# USBCONN_A_short.net
KiCad netlist of a schematic drawn in Altium Designer
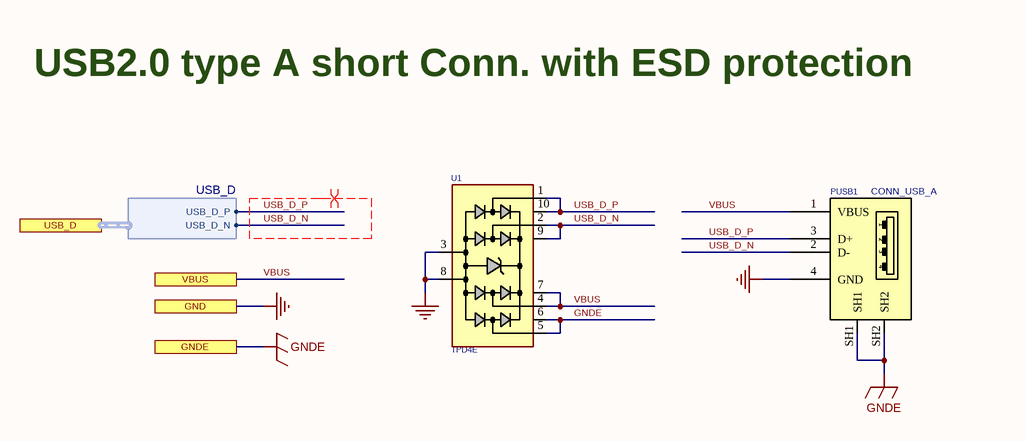
[diagram p0: USBCONN_A_short.SchDoc]

(export (version "E")
  (design (tool "Eeschema 10.0.6"))
  (components
    (comp (ref "PUSB1")
      (value "CONN_USB_A")
      (footprint "USB_A_REC_RA_THD_S")
      (description "CONN, USB, A, RECEPTACLE, R/A, THD")
      (fields (field (name "MANF_P#") "USB1125"))
      (libsource (lib "conn_usb") (part "CONN_USB_A_REC_RA_THD_SHORT"))
    )
    (comp (ref "U1")
      (value "TPD4E")
      (footprint "SON50_10_2510")
      (description "TVS, ESD PROTECT, 4CH,")
      (fields (field (name "MANF_P#") "TPD4E05U06DQA") (field (name "MANF") "Texas Instruments"))
      (libsource (lib "protect_tvs_esd_fuse") (part "TVS_X4_TPD4E05U06"))
    )
  )
  (nets
    (net (code "2") (name "/USB_D_N") (class "Default")
      (node (ref "PUSB1") (pin "2") (pinfunction "D-_2") (pintype "passive"))
      (node (ref "U1") (pin "2") (pinfunction "2_2") (pintype "passive"))
      (node (ref "U1") (pin "9") (pinfunction "9_9") (pintype "passive"))
    )
    (net (code "3") (name "/USB_D_P") (class "Default")
      (node (ref "PUSB1") (pin "3") (pinfunction "D+_3") (pintype "passive"))
      (node (ref "U1") (pin "1") (pinfunction "1_1") (pintype "passive"))
      (node (ref "U1") (pin "10") (pinfunction "10_10") (pintype "passive"))
    )
    (net (code "4") (name "/VBUS") (class "Default")
      (node (ref "PUSB1") (pin "1") (pinfunction "VBUS_1") (pintype "passive"))
      (node (ref "U1") (pin "4") (pinfunction "4_4") (pintype "passive"))
      (node (ref "U1") (pin "7") (pinfunction "7_7") (pintype "passive"))
    )
    (net (code "6") (name "GND") (class "Default")
      (node (ref "PUSB1") (pin "4") (pinfunction "GND_4") (pintype "passive"))
      (node (ref "U1") (pin "3") (pinfunction "3_3") (pintype "passive"))
      (node (ref "U1") (pin "8") (pinfunction "8_8") (pintype "passive"))
    )
    (net (code "7") (name "GNDE") (class "Default")
      (node (ref "PUSB1") (pin "SH1") (pinfunction "SH1_SH1") (pintype "passive"))
      (node (ref "PUSB1") (pin "SH2") (pinfunction "SH2_SH2") (pintype "passive"))
      (node (ref "U1") (pin "5") (pinfunction "5_5") (pintype "passive"))
      (node (ref "U1") (pin "6") (pinfunction "6_6") (pintype "passive"))
    )
  )
)
